# 1-Schematic_ac_todc.net
KiCad netlist of a schematic drawn in EasyEDA
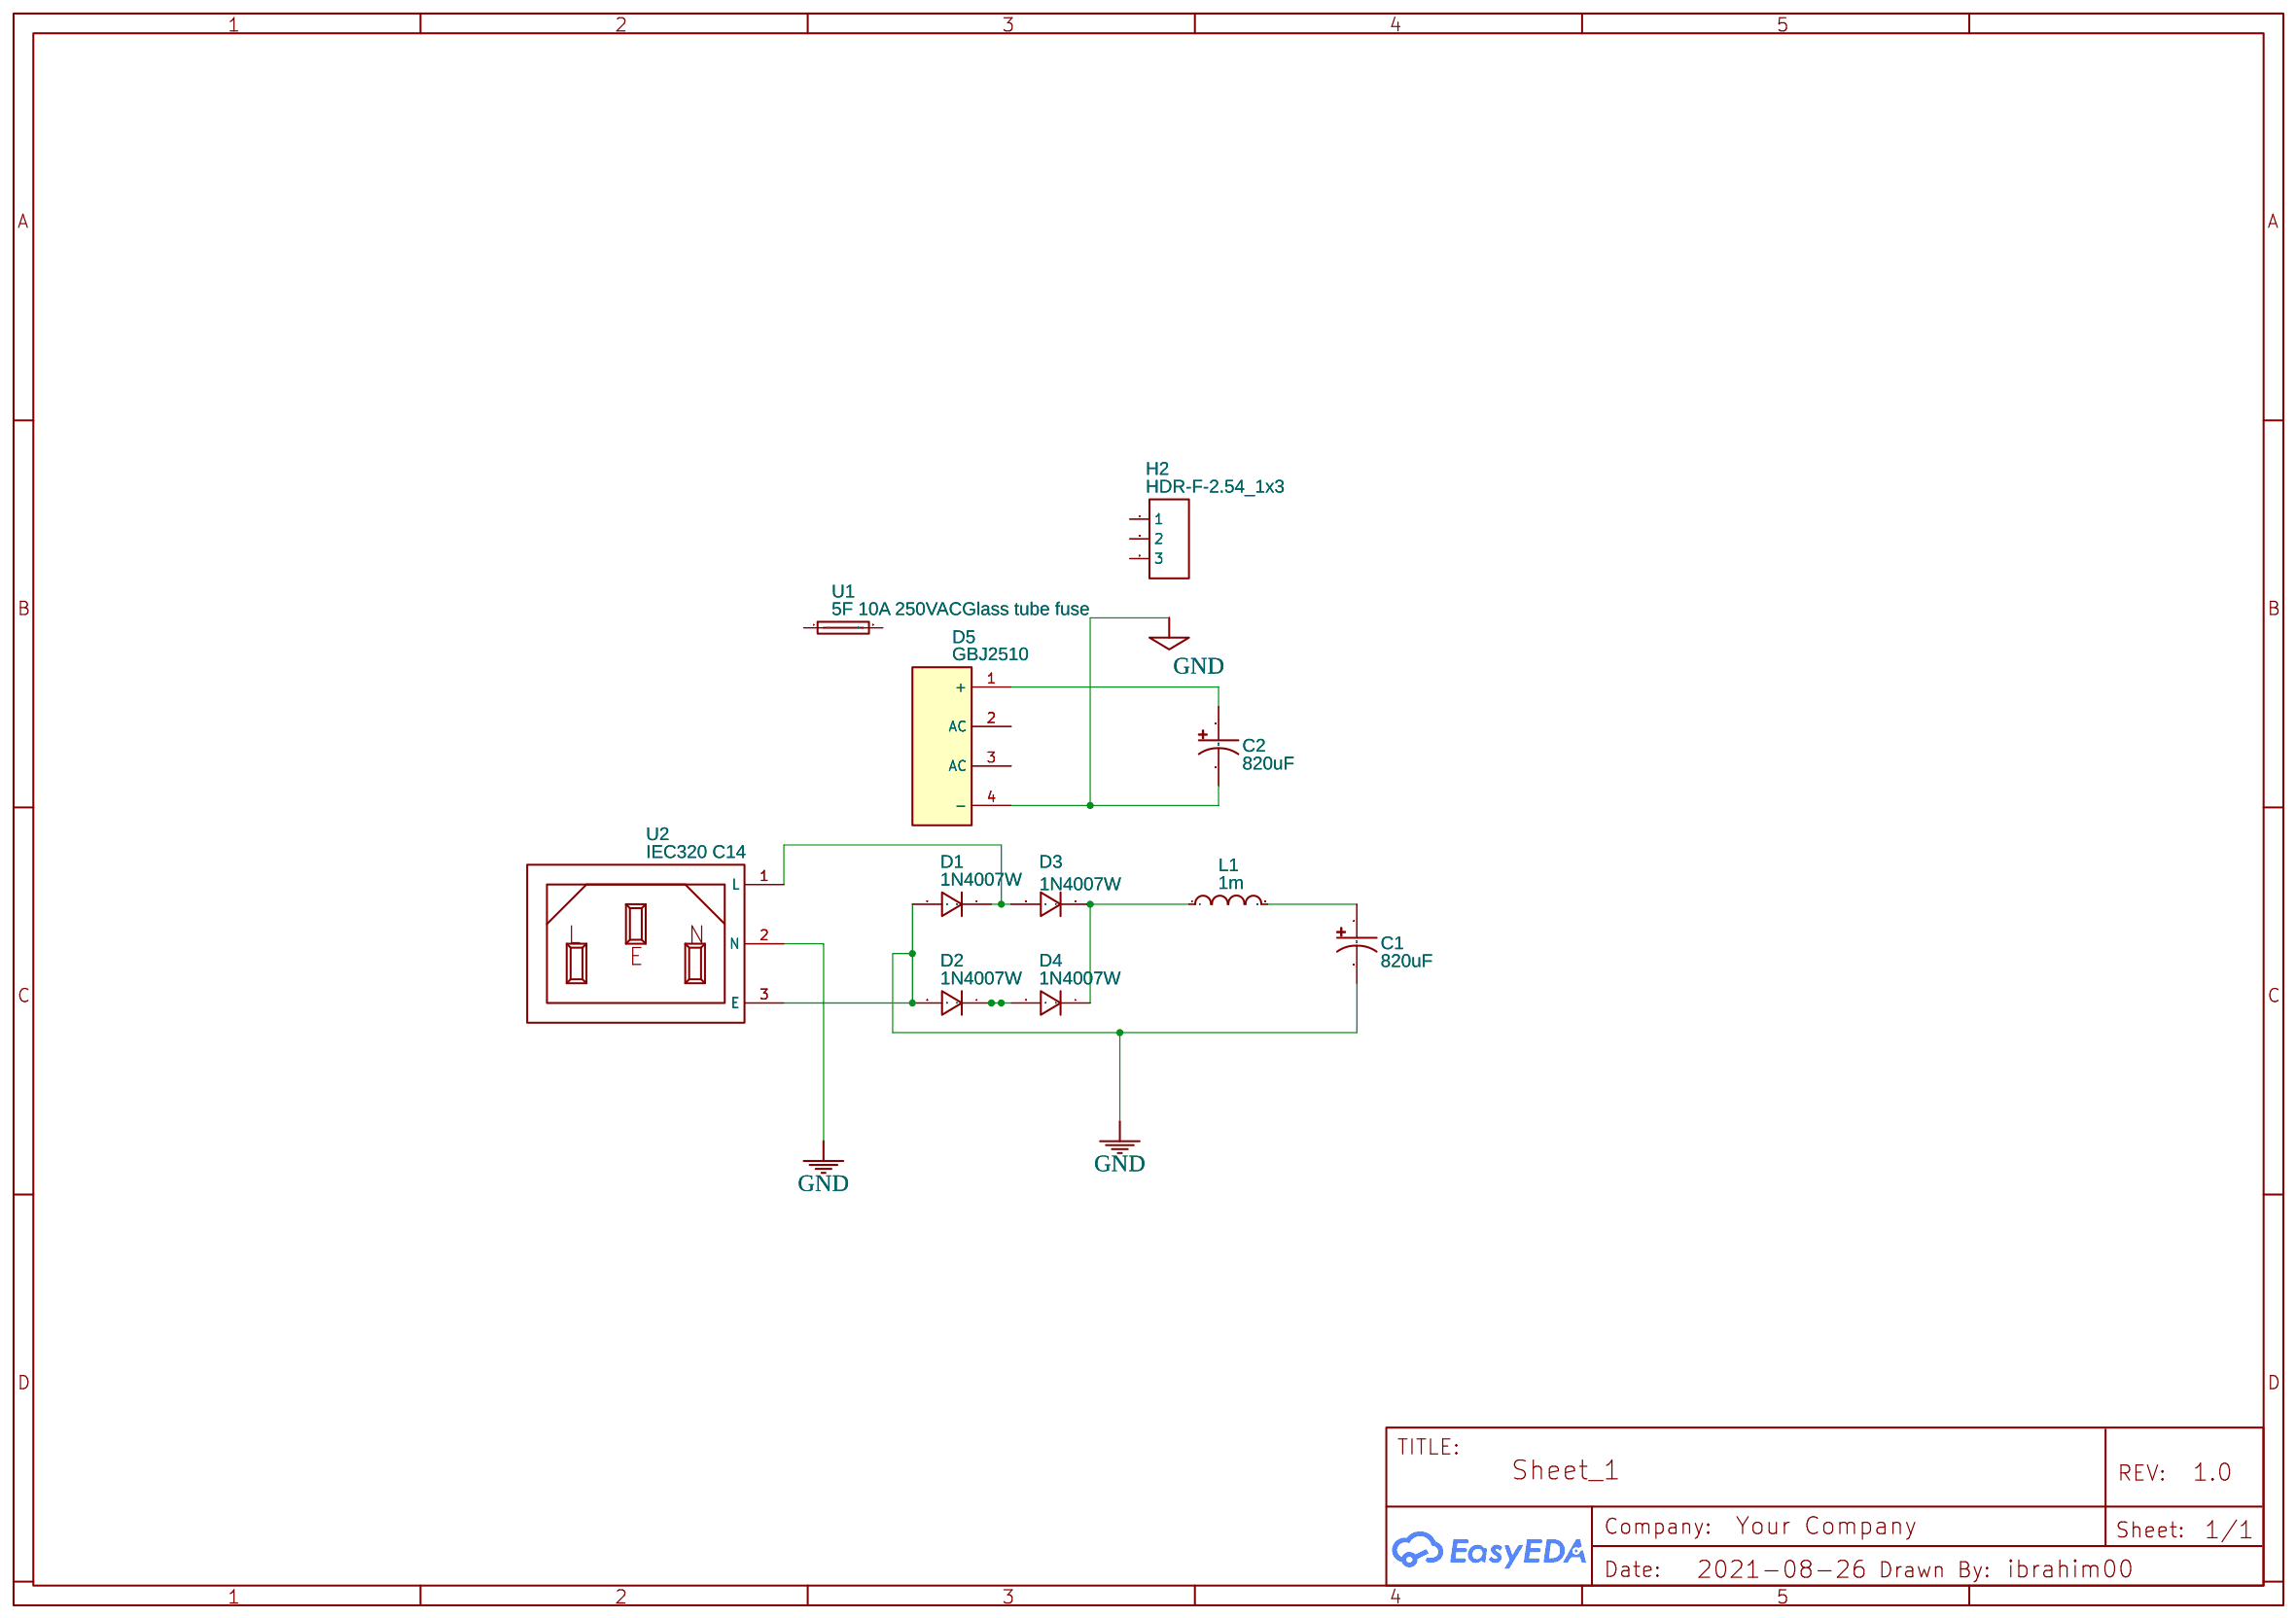
[diagram p0: schematic sheet]

(export (version "E")
  (design (tool "Eeschema 10.0.6"))
  (components
    (comp (ref "C1")
      (value "820uF")
      (fields
        (field (name "BOM_Manufacturer Part") "TDC-400V820-35*45")
        (field (name "BOM_Supplier Part") "C350238")
      )
      (libsource (lib "") (part "TDC-400V820-35*45"))
    )
    (comp (ref "C2")
      (value "820uF")
      (fields
        (field (name "BOM_Manufacturer Part") "TDC-400V820-35*45")
        (field (name "BOM_Supplier Part") "C350238")
      )
      (libsource (lib "") (part "TDC-400V820-35*45"))
    )
    (comp (ref "D1")
      (value "1N4007W")
      (fields (field (name "BOM_Supplier Part") "C328592"))
      (libsource (lib "") (part "1N4007W"))
    )
    (comp (ref "D2")
      (value "1N4007W")
      (fields (field (name "BOM_Supplier Part") "C328592"))
      (libsource (lib "") (part "1N4007W"))
    )
    (comp (ref "D3")
      (value "1N4007W")
      (fields (field (name "BOM_Supplier Part") "C328592"))
      (libsource (lib "") (part "1N4007W"))
    )
    (comp (ref "D4")
      (value "1N4007W")
      (fields (field (name "BOM_Supplier Part") "C328592"))
      (libsource (lib "") (part "1N4007W"))
    )
    (comp (ref "D5")
      (value "GBJ2510")
      (fields (field (name "BOM_Supplier Part") "C27523"))
      (libsource (lib "") (part "GBJ2510"))
    )
    (comp (ref "H2")
      (value "HDR-F-2.54_1x3")
      (fields (field (name "BOM_Supplier Part") "C146690"))
      (libsource (lib "") (part "HDR-F-2.54_1x3"))
    )
    (comp (ref "L1") (value "1m") (libsource (lib "") (part "L0603_US")))
    (comp (ref "U1")
      (value "5F 10A 250VACGlass tube fuse")
      (fields (field (name "BOM_Supplier Part") "C3122"))
      (libsource (lib "") (part "5F 10A 250VACGlass tube fuse"))
    )
    (comp (ref "U2") (value "IEC320 C14") (libsource (lib "") (part "IEC320 C14")))
  )
  (nets
    (net (code "1") (name "GND") (class "Default")
      (node (ref "C1") (pin "2") (pinfunction "2_2") (pintype "unspecified"))
      (node (ref "C2") (pin "2") (pinfunction "2_2") (pintype "unspecified"))
      (node (ref "D1") (pin "2") (pinfunction "2_2") (pintype "unspecified"))
      (node (ref "D2") (pin "2") (pinfunction "2_2") (pintype "unspecified"))
      (node (ref "D5") (pin "4") (pinfunction "-_4") (pintype "input"))
      (node (ref "U2") (pin "2") (pinfunction "N_2") (pintype "unspecified"))
      (node (ref "U2") (pin "3") (pinfunction "E_3") (pintype "unspecified"))
    )
    (net (code "2") (name "Net-(C1-Pad1)") (class "Default")
      (node (ref "C1") (pin "1") (pinfunction "1_1") (pintype "unspecified"))
      (node (ref "L1") (pin "2") (pinfunction "2_2") (pintype "unspecified"))
    )
    (net (code "3") (name "Net-(D2-Pad1)") (class "Default")
      (node (ref "D2") (pin "1") (pinfunction "1_1") (pintype "unspecified"))
      (node (ref "D4") (pin "2") (pinfunction "2_2") (pintype "unspecified"))
    )
    (net (code "4") (name "Net-(D3-Pad1)") (class "Default")
      (node (ref "D3") (pin "1") (pinfunction "1_1") (pintype "unspecified"))
      (node (ref "D4") (pin "1") (pinfunction "1_1") (pintype "unspecified"))
      (node (ref "L1") (pin "1") (pinfunction "1_1") (pintype "unspecified"))
    )
    (net (code "5") (name "Net-(D5-+)") (class "Default")
      (node (ref "C2") (pin "1") (pinfunction "1_1") (pintype "unspecified"))
      (node (ref "D5") (pin "1") (pinfunction "+_1") (pintype "input"))
    )
    (net (code "6") (name "Net-(U2-L)") (class "Default")
      (node (ref "D1") (pin "1") (pinfunction "1_1") (pintype "unspecified"))
      (node (ref "D3") (pin "2") (pinfunction "2_2") (pintype "unspecified"))
      (node (ref "U2") (pin "1") (pinfunction "L_1") (pintype "unspecified"))
    )
    (net (code "7") (name "unconnected-(D5-AC-Pad2)") (class "Default")
      (node (ref "D5") (pin "2") (pinfunction "AC_2") (pintype "input"))
    )
    (net (code "8") (name "unconnected-(D5-AC-Pad3)") (class "Default")
      (node (ref "D5") (pin "3") (pinfunction "AC_3") (pintype "input"))
    )
    (net (code "9") (name "unconnected-(H2-Pad1)") (class "Default")
      (node (ref "H2") (pin "1") (pinfunction "1_1") (pintype "input"))
    )
    (net (code "10") (name "unconnected-(H2-Pad2)") (class "Default")
      (node (ref "H2") (pin "2") (pinfunction "2_2") (pintype "input"))
    )
    (net (code "11") (name "unconnected-(H2-Pad3)") (class "Default")
      (node (ref "H2") (pin "3") (pinfunction "3_3") (pintype "input"))
    )
    (net (code "12") (name "unconnected-(U1-Pad1)") (class "Default")
      (node (ref "U1") (pin "1") (pinfunction "1_1") (pintype "unspecified"))
    )
    (net (code "13") (name "unconnected-(U1-Pad2)") (class "Default")
      (node (ref "U1") (pin "2") (pinfunction "2_2") (pintype "unspecified"))
    )
  )
)
